# SNIFFR.net
KiCad netlist of a schematic drawn in EAGLE
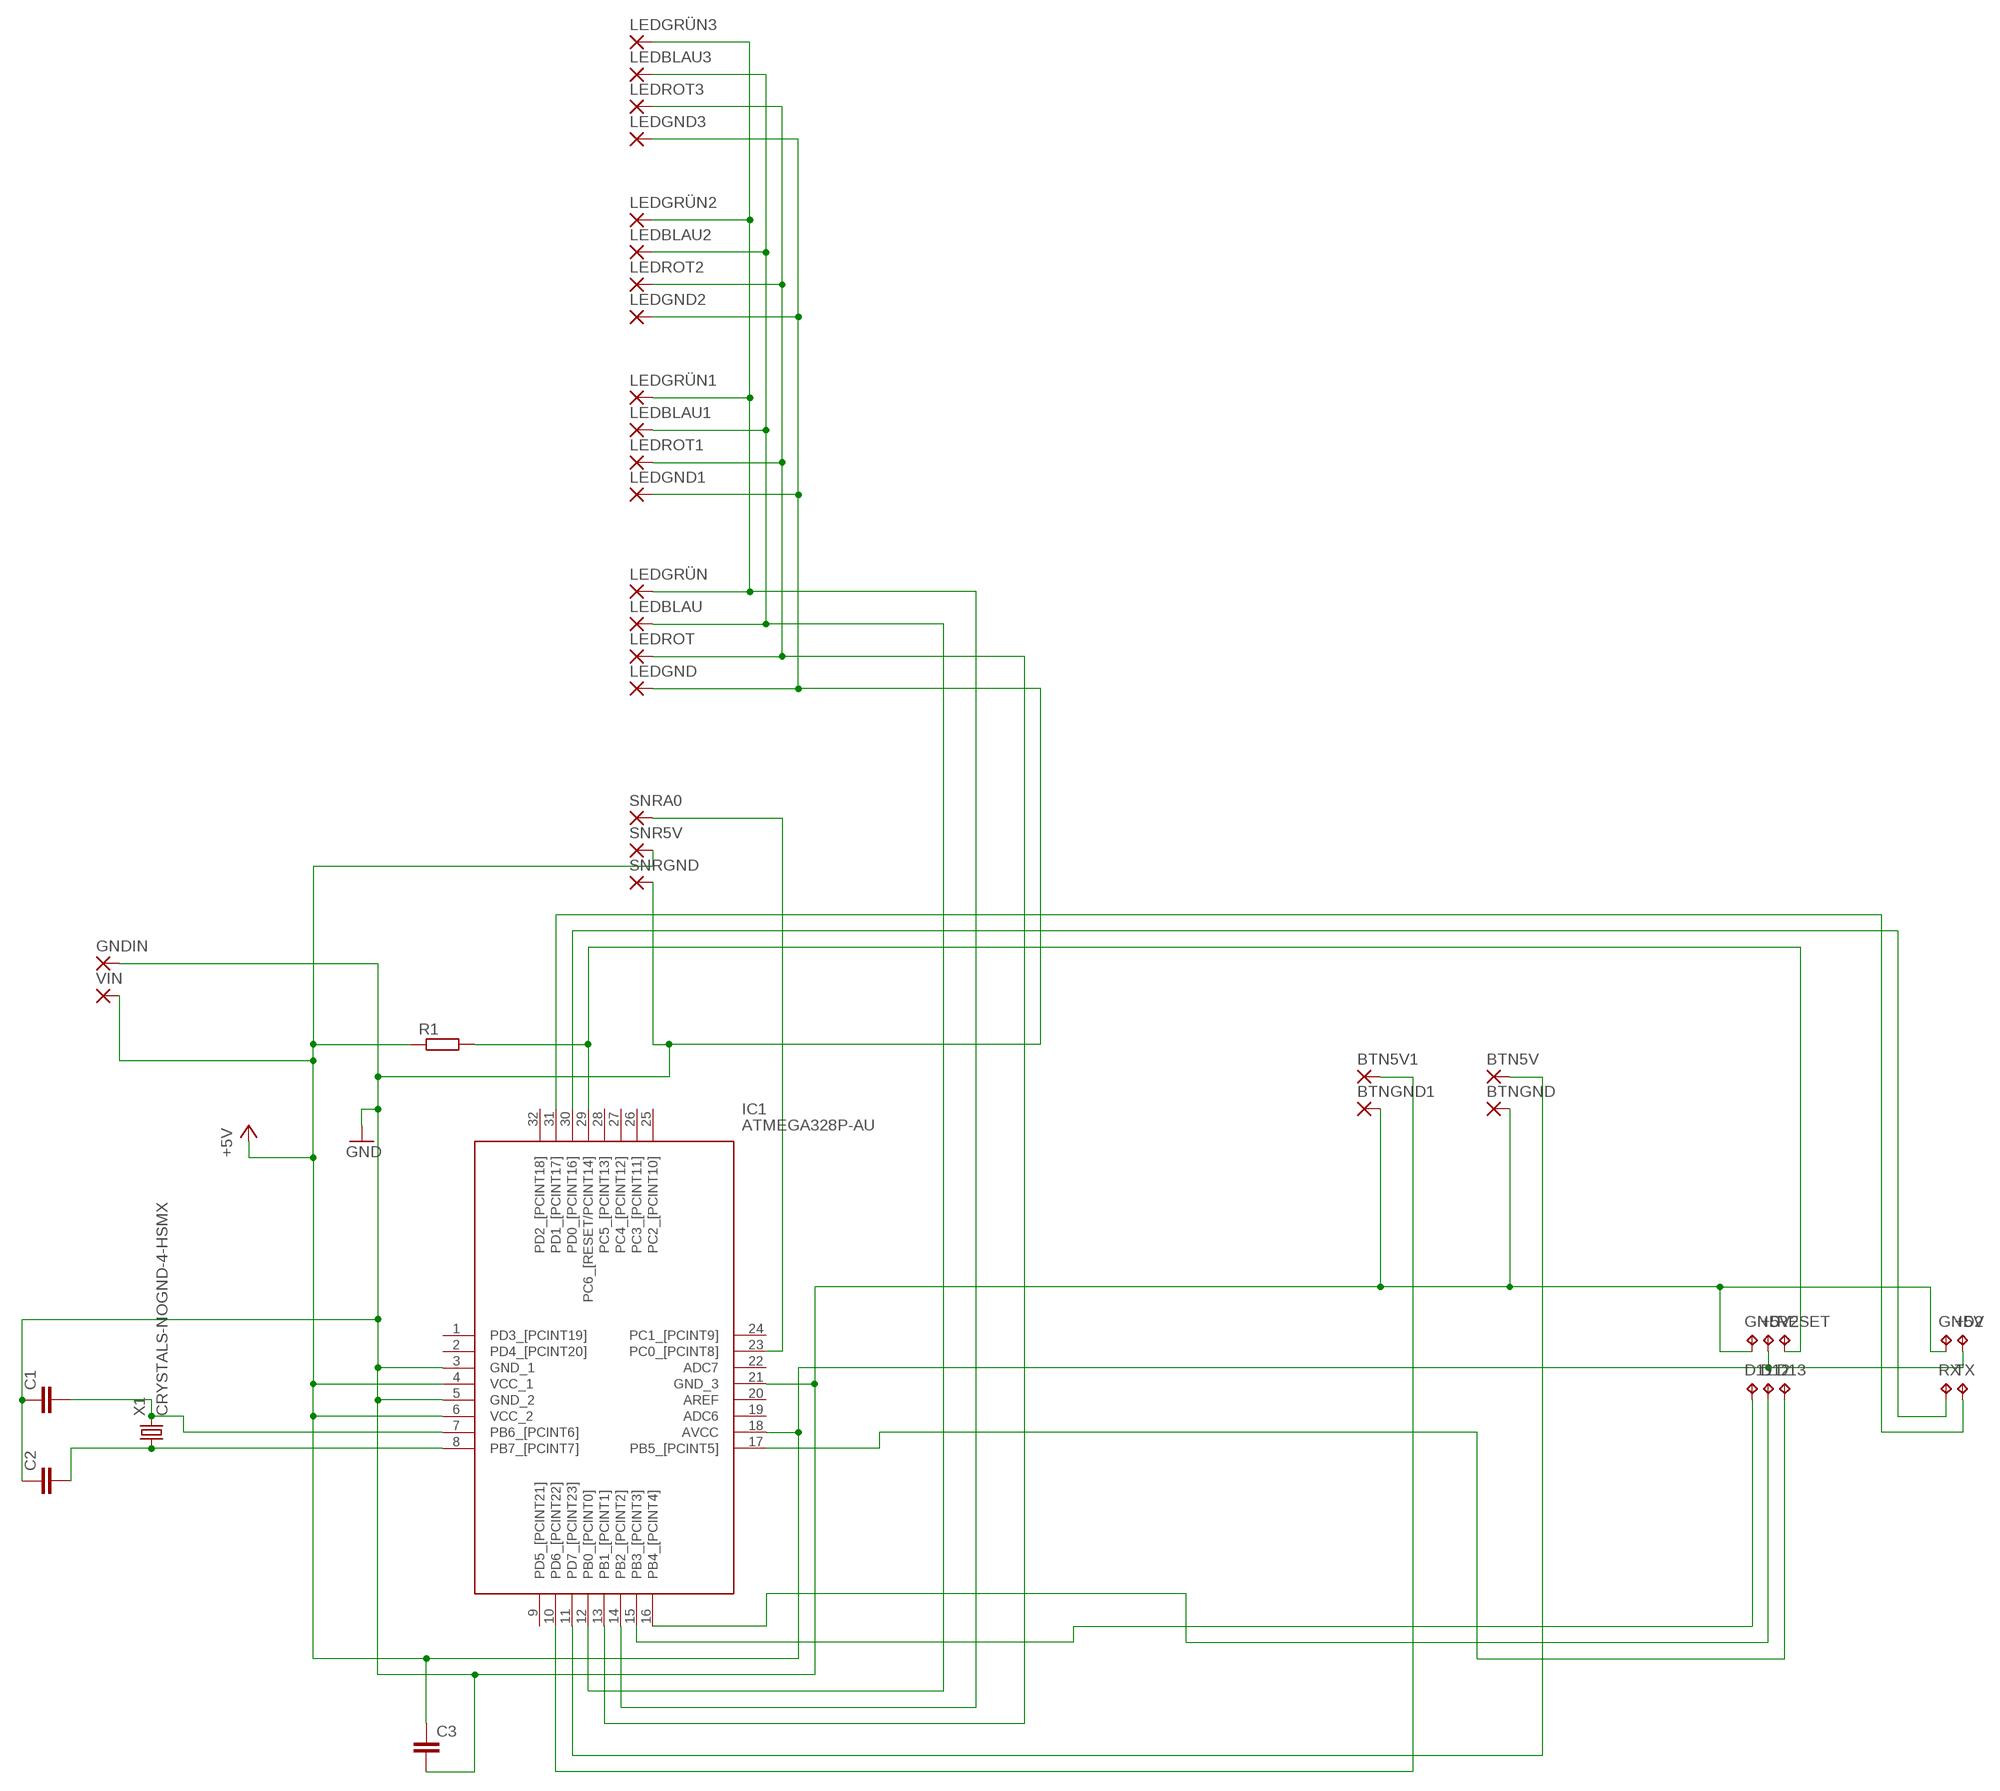
[diagram p0: schematic, sheet 1]

(export (version "E")
  (design (tool "Eeschema 10.0.6"))
  (components
    (comp (ref "+5V")
      (value "TPTP15SQ")
      (footprint "eagle-import:TP15SQ")
      (libsource (lib "eagle-import") (part "TPTP15SQ"))
    )
    (comp (ref "+5V2")
      (value "TPTP15SQ")
      (footprint "eagle-import:TP15SQ")
      (libsource (lib "eagle-import") (part "TPTP15SQ"))
    )
    (comp (ref "BTN5V")
      (value "2,15/1,0")
      (footprint "eagle-import:2,15_1,0")
      (libsource (lib "eagle-import") (part "2,15/1,0"))
    )
    (comp (ref "BTN5V1")
      (value "2,15/1,0")
      (footprint "eagle-import:2,15_1,0")
      (libsource (lib "eagle-import") (part "2,15/1,0"))
    )
    (comp (ref "BTNGND")
      (value "2,15/1,0")
      (footprint "eagle-import:2,15_1,0")
      (libsource (lib "eagle-import") (part "2,15/1,0"))
    )
    (comp (ref "BTNGND1")
      (value "2,15/1,0")
      (footprint "eagle-import:2,15_1,0")
      (libsource (lib "eagle-import") (part "2,15/1,0"))
    )
    (comp (ref "C1")
      (value "C-EUC0805")
      (footprint "eagle-import:C0805")
      (libsource (lib "eagle-import") (part "C-EUC0805"))
    )
    (comp (ref "C2")
      (value "C-EUC0805")
      (footprint "eagle-import:C0805")
      (libsource (lib "eagle-import") (part "C-EUC0805"))
    )
    (comp (ref "C3")
      (value "C-EUC0805")
      (footprint "eagle-import:C0805")
      (libsource (lib "eagle-import") (part "C-EUC0805"))
    )
    (comp (ref "D11")
      (value "TPTP15SQ")
      (footprint "eagle-import:TP15SQ")
      (libsource (lib "eagle-import") (part "TPTP15SQ"))
    )
    (comp (ref "D12")
      (value "TPTP15SQ")
      (footprint "eagle-import:TP15SQ")
      (libsource (lib "eagle-import") (part "TPTP15SQ"))
    )
    (comp (ref "D13")
      (value "TPTP15SQ")
      (footprint "eagle-import:TP15SQ")
      (libsource (lib "eagle-import") (part "TPTP15SQ"))
    )
    (comp (ref "GND")
      (value "TPTP15SQ")
      (footprint "eagle-import:TP15SQ")
      (libsource (lib "eagle-import") (part "TPTP15SQ"))
    )
    (comp (ref "GND2")
      (value "TPTP15SQ")
      (footprint "eagle-import:TP15SQ")
      (libsource (lib "eagle-import") (part "TPTP15SQ"))
    )
    (comp (ref "GNDIN")
      (value "2,15/1,0")
      (footprint "eagle-import:2,15_1,0")
      (libsource (lib "eagle-import") (part "2,15/1,0"))
    )
    (comp (ref "IC1")
      (value "ATMEGA328P-AU")
      (footprint "eagle-import:QFP80P900X900X120-32N")
      (fields (field (name "MOUSER_PART_NUMBER") "556-ATMEGA328P-AU"))
      (libsource (lib "eagle-import") (part "ATMEGA328P-AU"))
    )
    (comp (ref "LEDBLAU")
      (value "2,15/1,0")
      (footprint "eagle-import:2,15_1,0")
      (libsource (lib "eagle-import") (part "2,15/1,0"))
    )
    (comp (ref "LEDBLAU1")
      (value "2,15/1,0")
      (footprint "eagle-import:2,15_1,0")
      (libsource (lib "eagle-import") (part "2,15/1,0"))
    )
    (comp (ref "LEDBLAU2")
      (value "2,15/1,0")
      (footprint "eagle-import:2,15_1,0")
      (libsource (lib "eagle-import") (part "2,15/1,0"))
    )
    (comp (ref "LEDBLAU3")
      (value "2,15/1,0")
      (footprint "eagle-import:2,15_1,0")
      (libsource (lib "eagle-import") (part "2,15/1,0"))
    )
    (comp (ref "LEDGND")
      (value "2,15/1,0")
      (footprint "eagle-import:2,15_1,0")
      (libsource (lib "eagle-import") (part "2,15/1,0"))
    )
    (comp (ref "LEDGND1")
      (value "2,15/1,0")
      (footprint "eagle-import:2,15_1,0")
      (libsource (lib "eagle-import") (part "2,15/1,0"))
    )
    (comp (ref "LEDGND2")
      (value "2,15/1,0")
      (footprint "eagle-import:2,15_1,0")
      (libsource (lib "eagle-import") (part "2,15/1,0"))
    )
    (comp (ref "LEDGND3")
      (value "2,15/1,0")
      (footprint "eagle-import:2,15_1,0")
      (libsource (lib "eagle-import") (part "2,15/1,0"))
    )
    (comp (ref "LEDGRÜN")
      (value "2,15/1,0")
      (footprint "eagle-import:2,15_1,0")
      (libsource (lib "eagle-import") (part "2,15/1,0"))
    )
    (comp (ref "LEDGRÜN1")
      (value "2,15/1,0")
      (footprint "eagle-import:2,15_1,0")
      (libsource (lib "eagle-import") (part "2,15/1,0"))
    )
    (comp (ref "LEDGRÜN2")
      (value "2,15/1,0")
      (footprint "eagle-import:2,15_1,0")
      (libsource (lib "eagle-import") (part "2,15/1,0"))
    )
    (comp (ref "LEDGRÜN3")
      (value "2,15/1,0")
      (footprint "eagle-import:2,15_1,0")
      (libsource (lib "eagle-import") (part "2,15/1,0"))
    )
    (comp (ref "LEDROT")
      (value "2,15/1,0")
      (footprint "eagle-import:2,15_1,0")
      (libsource (lib "eagle-import") (part "2,15/1,0"))
    )
    (comp (ref "LEDROT1")
      (value "2,15/1,0")
      (footprint "eagle-import:2,15_1,0")
      (libsource (lib "eagle-import") (part "2,15/1,0"))
    )
    (comp (ref "LEDROT2")
      (value "2,15/1,0")
      (footprint "eagle-import:2,15_1,0")
      (libsource (lib "eagle-import") (part "2,15/1,0"))
    )
    (comp (ref "LEDROT3")
      (value "2,15/1,0")
      (footprint "eagle-import:2,15_1,0")
      (libsource (lib "eagle-import") (part "2,15/1,0"))
    )
    (comp (ref "R1")
      (value "R-EU_R0805")
      (footprint "eagle-import:R0805")
      (libsource (lib "eagle-import") (part "R-EU_R0805"))
    )
    (comp (ref "RESET")
      (value "TPTP15SQ")
      (footprint "eagle-import:TP15SQ")
      (libsource (lib "eagle-import") (part "TPTP15SQ"))
    )
    (comp (ref "RX")
      (value "TPTP15SQ")
      (footprint "eagle-import:TP15SQ")
      (libsource (lib "eagle-import") (part "TPTP15SQ"))
    )
    (comp (ref "SNR5V")
      (value "2,15/1,0")
      (footprint "eagle-import:2,15_1,0")
      (libsource (lib "eagle-import") (part "2,15/1,0"))
    )
    (comp (ref "SNRA0")
      (value "2,15/1,0")
      (footprint "eagle-import:2,15_1,0")
      (libsource (lib "eagle-import") (part "2,15/1,0"))
    )
    (comp (ref "SNRGND")
      (value "2,15/1,0")
      (footprint "eagle-import:2,15_1,0")
      (libsource (lib "eagle-import") (part "2,15/1,0"))
    )
    (comp (ref "TX")
      (value "TPTP15SQ")
      (footprint "eagle-import:TP15SQ")
      (libsource (lib "eagle-import") (part "TPTP15SQ"))
    )
    (comp (ref "VIN")
      (value "2,15/1,0")
      (footprint "eagle-import:2,15_1,0")
      (libsource (lib "eagle-import") (part "2,15/1,0"))
    )
    (comp (ref "X1")
      (value "CRYSTALS-NOGND-4-HSMX")
      (footprint "eagle-import:HC49-4-HSMX")
      (libsource (lib "eagle-import") (part "CRYSTALS-NOGND-4-HSMX"))
    )
  )
  (nets
    (net (code "1") (name "+5V") (class "Default")
      (node (ref "+5V") (pin "TP") (pinfunction "TP_TP") (pintype "input"))
      (node (ref "+5V2") (pin "TP") (pinfunction "TP_TP") (pintype "input"))
      (node (ref "C3") (pin "1") (pinfunction "1_1") (pintype "passive"))
      (node (ref "IC1") (pin "18") (pinfunction "AVCC_18") (pintype "power_in"))
      (node (ref "IC1") (pin "4") (pinfunction "VCC_1_4") (pintype "power_in"))
      (node (ref "IC1") (pin "6") (pinfunction "VCC_2_6") (pintype "power_in"))
      (node (ref "R1") (pin "1") (pinfunction "1_1") (pintype "passive"))
      (node (ref "SNR5V") (pin "1") (pinfunction "P_1") (pintype "passive"))
      (node (ref "VIN") (pin "1") (pinfunction "P_1") (pintype "passive"))
    )
    (net (code "2") (name "GND") (class "Default")
      (node (ref "BTNGND") (pin "1") (pinfunction "P_1") (pintype "passive"))
      (node (ref "BTNGND1") (pin "1") (pinfunction "P_1") (pintype "passive"))
      (node (ref "C1") (pin "1") (pinfunction "1_1") (pintype "passive"))
      (node (ref "C2") (pin "1") (pinfunction "1_1") (pintype "passive"))
      (node (ref "C3") (pin "2") (pinfunction "2_2") (pintype "passive"))
      (node (ref "GND") (pin "TP") (pinfunction "TP_TP") (pintype "input"))
      (node (ref "GND2") (pin "TP") (pinfunction "TP_TP") (pintype "input"))
      (node (ref "GNDIN") (pin "1") (pinfunction "P_1") (pintype "passive"))
      (node (ref "IC1") (pin "21") (pinfunction "GND_3_21") (pintype "power_in"))
      (node (ref "IC1") (pin "3") (pinfunction "GND_1_3") (pintype "power_in"))
      (node (ref "IC1") (pin "5") (pinfunction "GND_2_5") (pintype "power_in"))
      (node (ref "LEDGND") (pin "1") (pinfunction "P_1") (pintype "passive"))
      (node (ref "LEDGND1") (pin "1") (pinfunction "P_1") (pintype "passive"))
      (node (ref "LEDGND2") (pin "1") (pinfunction "P_1") (pintype "passive"))
      (node (ref "LEDGND3") (pin "1") (pinfunction "P_1") (pintype "passive"))
      (node (ref "SNRGND") (pin "1") (pinfunction "P_1") (pintype "passive"))
    )
    (net (code "3") (name "Net-(BTN5V-P)") (class "Default")
      (node (ref "BTN5V") (pin "1") (pinfunction "P_1") (pintype "passive"))
      (node (ref "IC1") (pin "11") (pinfunction "PD7_[PCINT23]_11") (pintype "bidirectional"))
    )
    (net (code "4") (name "Net-(BTN5V1-P)") (class "Default")
      (node (ref "BTN5V1") (pin "1") (pinfunction "P_1") (pintype "passive"))
      (node (ref "IC1") (pin "10") (pinfunction "PD6_[PCINT22]_10") (pintype "bidirectional"))
    )
    (net (code "5") (name "Net-(IC1-PB0_[PCINT0])") (class "Default")
      (node (ref "IC1") (pin "12") (pinfunction "PB0_[PCINT0]_12") (pintype "bidirectional"))
      (node (ref "LEDBLAU") (pin "1") (pinfunction "P_1") (pintype "passive"))
      (node (ref "LEDBLAU1") (pin "1") (pinfunction "P_1") (pintype "passive"))
      (node (ref "LEDBLAU2") (pin "1") (pinfunction "P_1") (pintype "passive"))
      (node (ref "LEDBLAU3") (pin "1") (pinfunction "P_1") (pintype "passive"))
    )
    (net (code "6") (name "Net-(IC1-PB1_[PCINT1])") (class "Default")
      (node (ref "IC1") (pin "13") (pinfunction "PB1_[PCINT1]_13") (pintype "bidirectional"))
      (node (ref "LEDROT") (pin "1") (pinfunction "P_1") (pintype "passive"))
      (node (ref "LEDROT1") (pin "1") (pinfunction "P_1") (pintype "passive"))
      (node (ref "LEDROT2") (pin "1") (pinfunction "P_1") (pintype "passive"))
      (node (ref "LEDROT3") (pin "1") (pinfunction "P_1") (pintype "passive"))
    )
    (net (code "7") (name "Net-(IC1-PB2_[PCINT2])") (class "Default")
      (node (ref "IC1") (pin "14") (pinfunction "PB2_[PCINT2]_14") (pintype "bidirectional"))
      (node (ref "LEDGRÜN") (pin "1") (pinfunction "P_1") (pintype "passive"))
      (node (ref "LEDGRÜN1") (pin "1") (pinfunction "P_1") (pintype "passive"))
      (node (ref "LEDGRÜN2") (pin "1") (pinfunction "P_1") (pintype "passive"))
      (node (ref "LEDGRÜN3") (pin "1") (pinfunction "P_1") (pintype "passive"))
    )
    (net (code "8") (name "Net-(IC1-PB3_[PCINT3])") (class "Default")
      (node (ref "D11") (pin "TP") (pinfunction "TP_TP") (pintype "input"))
      (node (ref "IC1") (pin "15") (pinfunction "PB3_[PCINT3]_15") (pintype "bidirectional"))
    )
    (net (code "9") (name "Net-(IC1-PB4_[PCINT4])") (class "Default")
      (node (ref "D12") (pin "TP") (pinfunction "TP_TP") (pintype "input"))
      (node (ref "IC1") (pin "16") (pinfunction "PB4_[PCINT4]_16") (pintype "bidirectional"))
    )
    (net (code "10") (name "Net-(IC1-PB5_[PCINT5])") (class "Default")
      (node (ref "D13") (pin "TP") (pinfunction "TP_TP") (pintype "input"))
      (node (ref "IC1") (pin "17") (pinfunction "PB5_[PCINT5]_17") (pintype "bidirectional"))
    )
    (net (code "11") (name "Net-(IC1-PB6_[PCINT6])") (class "Default")
      (node (ref "C1") (pin "2") (pinfunction "2_2") (pintype "passive"))
      (node (ref "IC1") (pin "7") (pinfunction "PB6_[PCINT6]_7") (pintype "bidirectional"))
      (node (ref "X1") (pin "2") (pinfunction "2_2") (pintype "passive"))
    )
    (net (code "12") (name "Net-(IC1-PB7_[PCINT7])") (class "Default")
      (node (ref "C2") (pin "2") (pinfunction "2_2") (pintype "passive"))
      (node (ref "IC1") (pin "8") (pinfunction "PB7_[PCINT7]_8") (pintype "bidirectional"))
      (node (ref "X1") (pin "1") (pinfunction "1_1") (pintype "passive"))
    )
    (net (code "13") (name "Net-(IC1-PC0_[PCINT8])") (class "Default")
      (node (ref "IC1") (pin "23") (pinfunction "PC0_[PCINT8]_23") (pintype "bidirectional"))
      (node (ref "SNRA0") (pin "1") (pinfunction "P_1") (pintype "passive"))
    )
    (net (code "14") (name "Net-(IC1-PC6_[RESET{slash}PCINT14])") (class "Default")
      (node (ref "IC1") (pin "29") (pinfunction "PC6_[RESET/PCINT14]_29") (pintype "bidirectional"))
      (node (ref "R1") (pin "2") (pinfunction "2_2") (pintype "passive"))
      (node (ref "RESET") (pin "TP") (pinfunction "TP_TP") (pintype "input"))
    )
    (net (code "15") (name "Net-(IC1-PD0_[PCINT16])") (class "Default")
      (node (ref "IC1") (pin "30") (pinfunction "PD0_[PCINT16]_30") (pintype "bidirectional"))
      (node (ref "RX") (pin "TP") (pinfunction "TP_TP") (pintype "input"))
    )
    (net (code "16") (name "Net-(IC1-PD1_[PCINT17])") (class "Default")
      (node (ref "IC1") (pin "31") (pinfunction "PD1_[PCINT17]_31") (pintype "bidirectional"))
      (node (ref "TX") (pin "TP") (pinfunction "TP_TP") (pintype "input"))
    )
    (net (code "17") (name "unconnected-(IC1-ADC6-Pad19)") (class "Default")
      (node (ref "IC1") (pin "19") (pinfunction "ADC6_19") (pintype "bidirectional"))
    )
    (net (code "18") (name "unconnected-(IC1-ADC7-Pad22)") (class "Default")
      (node (ref "IC1") (pin "22") (pinfunction "ADC7_22") (pintype "bidirectional"))
    )
    (net (code "19") (name "unconnected-(IC1-AREF-Pad20)") (class "Default")
      (node (ref "IC1") (pin "20") (pinfunction "AREF_20") (pintype "bidirectional"))
    )
    (net (code "20") (name "unconnected-(IC1-PC1_[PCINT9]-Pad24)") (class "Default")
      (node (ref "IC1") (pin "24") (pinfunction "PC1_[PCINT9]_24") (pintype "bidirectional"))
    )
    (net (code "21") (name "unconnected-(IC1-PC2_[PCINT10]-Pad25)") (class "Default")
      (node (ref "IC1") (pin "25") (pinfunction "PC2_[PCINT10]_25") (pintype "bidirectional"))
    )
    (net (code "22") (name "unconnected-(IC1-PC3_[PCINT11]-Pad26)") (class "Default")
      (node (ref "IC1") (pin "26") (pinfunction "PC3_[PCINT11]_26") (pintype "bidirectional"))
    )
    (net (code "23") (name "unconnected-(IC1-PC4_[PCINT12]-Pad27)") (class "Default")
      (node (ref "IC1") (pin "27") (pinfunction "PC4_[PCINT12]_27") (pintype "bidirectional"))
    )
    (net (code "24") (name "unconnected-(IC1-PC5_[PCINT13]-Pad28)") (class "Default")
      (node (ref "IC1") (pin "28") (pinfunction "PC5_[PCINT13]_28") (pintype "bidirectional"))
    )
    (net (code "25") (name "unconnected-(IC1-PD2_[PCINT18]-Pad32)") (class "Default")
      (node (ref "IC1") (pin "32") (pinfunction "PD2_[PCINT18]_32") (pintype "bidirectional"))
    )
    (net (code "26") (name "unconnected-(IC1-PD3_[PCINT19]-Pad1)") (class "Default")
      (node (ref "IC1") (pin "1") (pinfunction "PD3_[PCINT19]_1") (pintype "bidirectional"))
    )
    (net (code "27") (name "unconnected-(IC1-PD4_[PCINT20]-Pad2)") (class "Default")
      (node (ref "IC1") (pin "2") (pinfunction "PD4_[PCINT20]_2") (pintype "bidirectional"))
    )
    (net (code "28") (name "unconnected-(IC1-PD5_[PCINT21]-Pad9)") (class "Default")
      (node (ref "IC1") (pin "9") (pinfunction "PD5_[PCINT21]_9") (pintype "bidirectional"))
    )
  )
)
